# Conn_B.net
KiCad netlist of a schematic drawn in Altium Designer
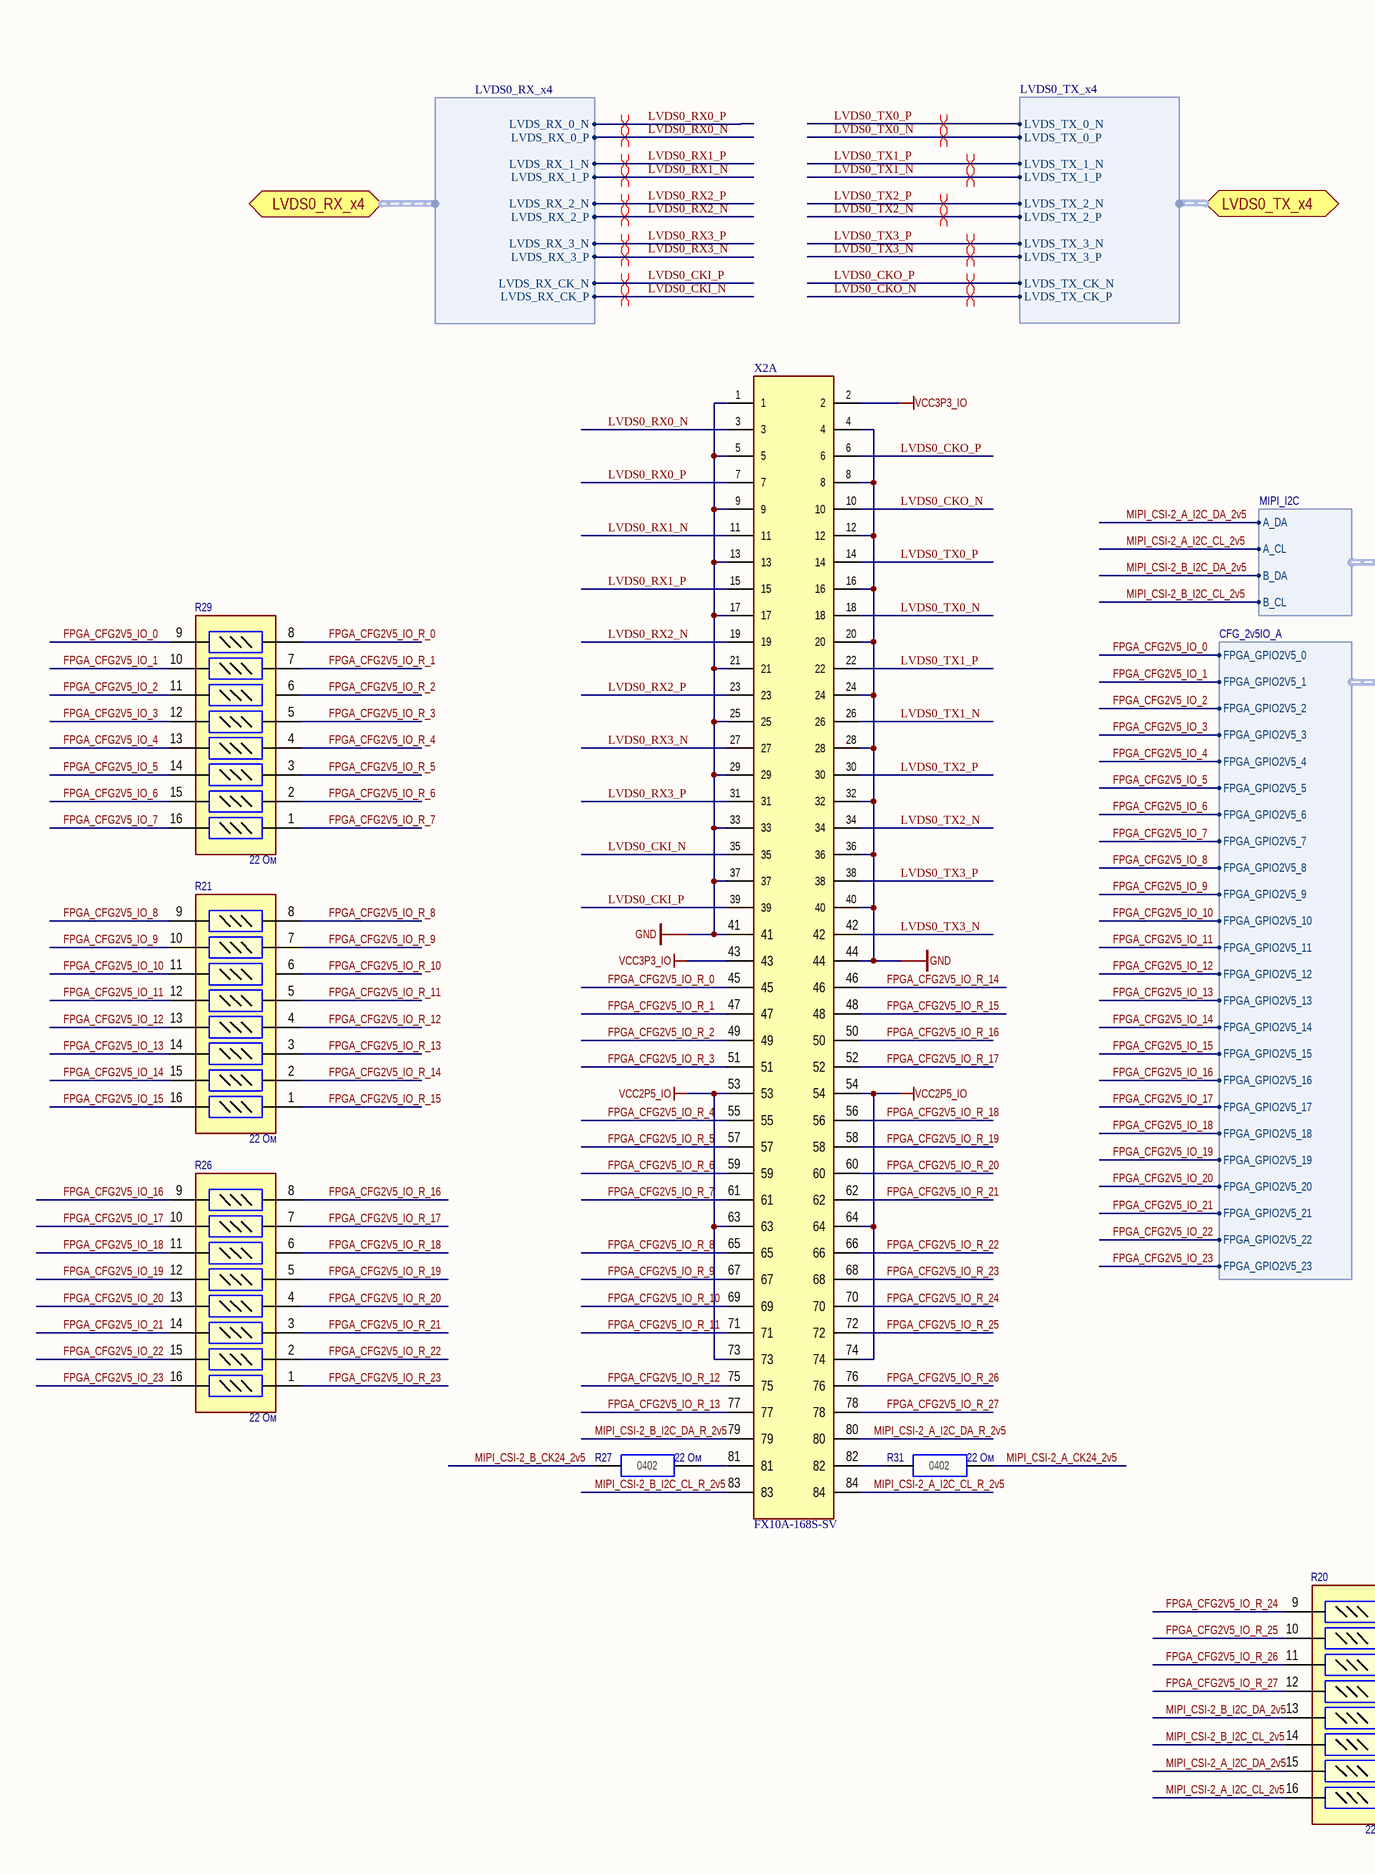
[diagram p0: Conn_B.SchDoc, left]
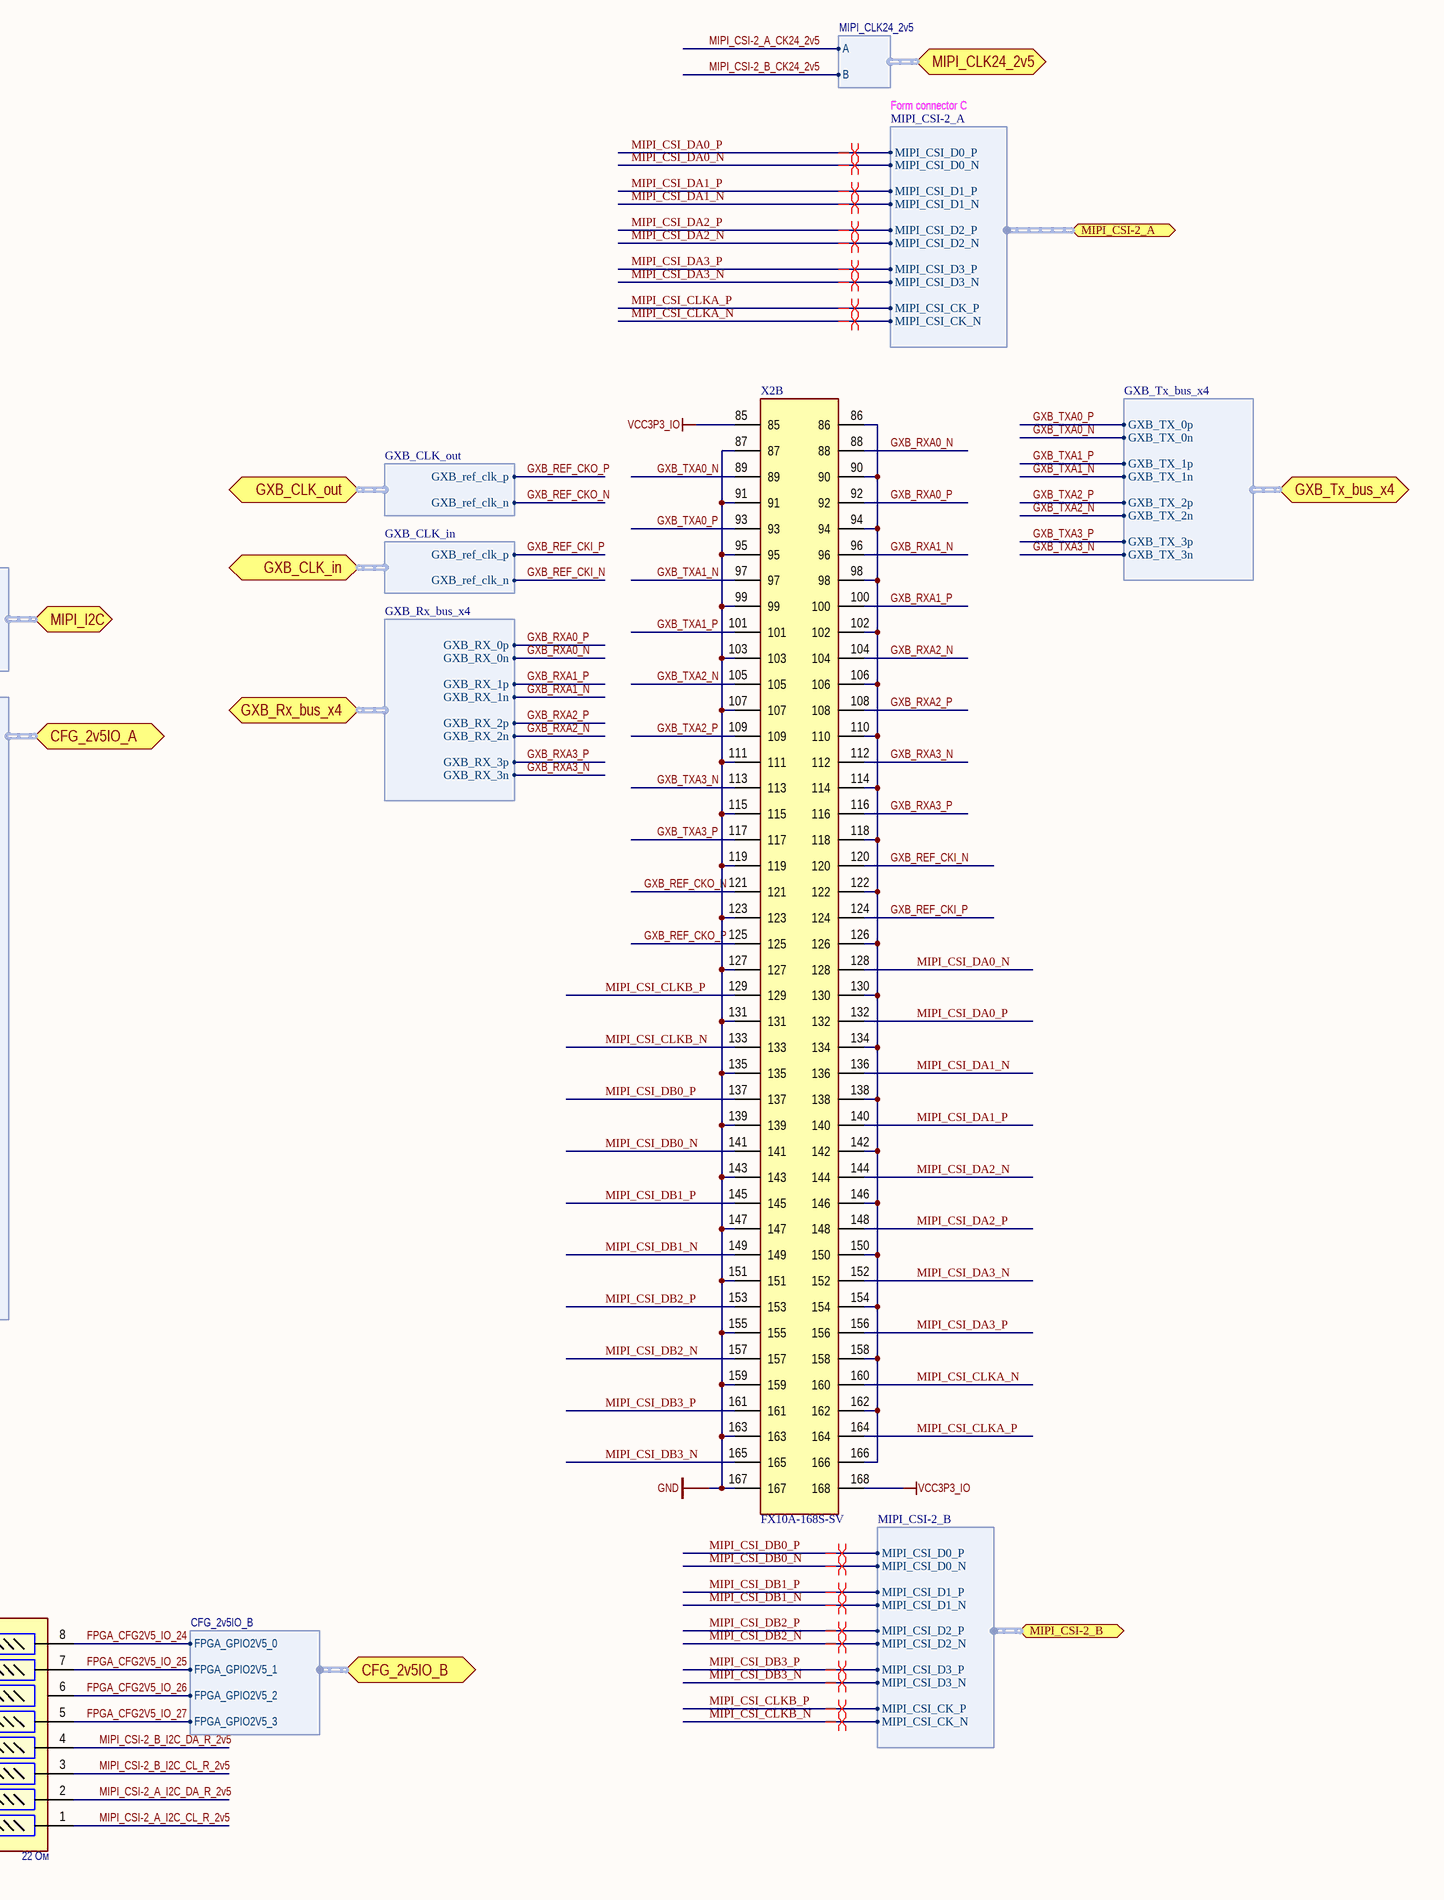
[diagram p1: Conn_B.SchDoc, right]

(export (version "E")
  (design (tool "Eeschema 10.0.6"))
  (components
    (comp (ref "R20")
      (value "22 Ом")
      (footprint "CAT16-J8")
      (description "Набор чип резисторов")
      (fields (field (name "Comment") "YC248-JR-07-22 Ом"))
      (libsource (lib "SD_IC") (part "YC248-JR-07-#"))
    )
    (comp (ref "R21")
      (value "22 Ом")
      (footprint "CAT16-J8")
      (description "Набор чип резисторов")
      (fields (field (name "Comment") "YC248-JR-07-22 Ом"))
      (libsource (lib "SD_IC") (part "YC248-JR-07-#"))
    )
    (comp (ref "R26")
      (value "22 Ом")
      (footprint "CAT16-J8")
      (description "Набор чип резисторов")
      (fields (field (name "Comment") "YC248-JR-07-22 Ом"))
      (libsource (lib "SD_IC") (part "YC248-JR-07-#"))
    )
    (comp (ref "R27")
      (value "22 Ом")
      (footprint "CR0402(1005)")
      (description "Чип резистор")
      (fields (field (name "TOLERANCE") "5%") (field (name "Comment") "CR0402-22 Ом-±5%"))
      (libsource (lib "Чип резисторы") (part "CR0402-#-±5%"))
    )
    (comp (ref "R29")
      (value "22 Ом")
      (footprint "CAT16-J8")
      (description "Набор чип резисторов")
      (fields (field (name "Comment") "YC248-JR-07-22 Ом"))
      (libsource (lib "SD_IC") (part "YC248-JR-07-#"))
    )
    (comp (ref "R31")
      (value "22 Ом")
      (footprint "CR0402(1005)")
      (description "Чип резистор")
      (fields (field (name "TOLERANCE") "5%") (field (name "Comment") "CR0402-22 Ом-±5%"))
      (libsource (lib "Чип резисторы") (part "CR0402-#-±5%"))
    )
    (comp (ref "X2")
      (value "FX10A-168S-SV")
      (footprint "FX10A-168S-SV")
      (libsource (lib "SD_IC") (part "FX10A-168S-SV"))
    )
  )
  (nets
    (net (code "13") (name "/FPGA_CFG2V5_IO_0") (class "Default")
      (node (ref "R29") (pin "9") (pintype "passive"))
    )
    (net (code "14") (name "/FPGA_CFG2V5_IO_1") (class "Default")
      (node (ref "R29") (pin "10") (pintype "passive"))
    )
    (net (code "15") (name "/FPGA_CFG2V5_IO_2") (class "Default")
      (node (ref "R29") (pin "11") (pintype "passive"))
    )
    (net (code "16") (name "/FPGA_CFG2V5_IO_3") (class "Default")
      (node (ref "R29") (pin "12") (pintype "passive"))
    )
    (net (code "17") (name "/FPGA_CFG2V5_IO_4") (class "Default")
      (node (ref "R29") (pin "13") (pintype "passive"))
    )
    (net (code "18") (name "/FPGA_CFG2V5_IO_5") (class "Default")
      (node (ref "R29") (pin "14") (pintype "passive"))
    )
    (net (code "19") (name "/FPGA_CFG2V5_IO_6") (class "Default")
      (node (ref "R29") (pin "15") (pintype "passive"))
    )
    (net (code "20") (name "/FPGA_CFG2V5_IO_7") (class "Default")
      (node (ref "R29") (pin "16") (pintype "passive"))
    )
    (net (code "21") (name "/FPGA_CFG2V5_IO_8") (class "Default")
      (node (ref "R21") (pin "9") (pintype "passive"))
    )
    (net (code "22") (name "/FPGA_CFG2V5_IO_9") (class "Default")
      (node (ref "R21") (pin "10") (pintype "passive"))
    )
    (net (code "23") (name "/FPGA_CFG2V5_IO_10") (class "Default")
      (node (ref "R21") (pin "11") (pintype "passive"))
    )
    (net (code "24") (name "/FPGA_CFG2V5_IO_11") (class "Default")
      (node (ref "R21") (pin "12") (pintype "passive"))
    )
    (net (code "25") (name "/FPGA_CFG2V5_IO_12") (class "Default")
      (node (ref "R21") (pin "13") (pintype "passive"))
    )
    (net (code "26") (name "/FPGA_CFG2V5_IO_13") (class "Default")
      (node (ref "R21") (pin "14") (pintype "passive"))
    )
    (net (code "27") (name "/FPGA_CFG2V5_IO_14") (class "Default")
      (node (ref "R21") (pin "15") (pintype "passive"))
    )
    (net (code "28") (name "/FPGA_CFG2V5_IO_15") (class "Default")
      (node (ref "R21") (pin "16") (pintype "passive"))
    )
    (net (code "29") (name "/FPGA_CFG2V5_IO_16") (class "Default")
      (node (ref "R26") (pin "9") (pintype "passive"))
    )
    (net (code "30") (name "/FPGA_CFG2V5_IO_17") (class "Default")
      (node (ref "R26") (pin "10") (pintype "passive"))
    )
    (net (code "31") (name "/FPGA_CFG2V5_IO_18") (class "Default")
      (node (ref "R26") (pin "11") (pintype "passive"))
    )
    (net (code "32") (name "/FPGA_CFG2V5_IO_19") (class "Default")
      (node (ref "R26") (pin "12") (pintype "passive"))
    )
    (net (code "33") (name "/FPGA_CFG2V5_IO_20") (class "Default")
      (node (ref "R26") (pin "13") (pintype "passive"))
    )
    (net (code "34") (name "/FPGA_CFG2V5_IO_21") (class "Default")
      (node (ref "R26") (pin "14") (pintype "passive"))
    )
    (net (code "35") (name "/FPGA_CFG2V5_IO_22") (class "Default")
      (node (ref "R26") (pin "15") (pintype "passive"))
    )
    (net (code "36") (name "/FPGA_CFG2V5_IO_23") (class "Default")
      (node (ref "R26") (pin "16") (pintype "passive"))
    )
    (net (code "37") (name "/FPGA_CFG2V5_IO_24") (class "Default")
      (node (ref "R20") (pin "8") (pintype "passive"))
    )
    (net (code "38") (name "/FPGA_CFG2V5_IO_25") (class "Default")
      (node (ref "R20") (pin "7") (pintype "passive"))
    )
    (net (code "39") (name "/FPGA_CFG2V5_IO_26") (class "Default")
      (node (ref "R20") (pin "6") (pintype "passive"))
    )
    (net (code "40") (name "/FPGA_CFG2V5_IO_27") (class "Default")
      (node (ref "R20") (pin "5") (pintype "passive"))
    )
    (net (code "41") (name "/FPGA_CFG2V5_IO_R_0") (class "Default")
      (node (ref "R29") (pin "8") (pintype "passive"))
      (node (ref "X2") (pin "45") (pinfunction "45_45") (pintype "passive"))
    )
    (net (code "42") (name "/FPGA_CFG2V5_IO_R_1") (class "Default")
      (node (ref "R29") (pin "7") (pintype "passive"))
      (node (ref "X2") (pin "47") (pinfunction "47_47") (pintype "passive"))
    )
    (net (code "43") (name "/FPGA_CFG2V5_IO_R_2") (class "Default")
      (node (ref "R29") (pin "6") (pintype "passive"))
      (node (ref "X2") (pin "49") (pinfunction "49_49") (pintype "passive"))
    )
    (net (code "44") (name "/FPGA_CFG2V5_IO_R_3") (class "Default")
      (node (ref "R29") (pin "5") (pintype "passive"))
      (node (ref "X2") (pin "51") (pinfunction "51_51") (pintype "passive"))
    )
    (net (code "45") (name "/FPGA_CFG2V5_IO_R_4") (class "Default")
      (node (ref "R29") (pin "4") (pintype "passive"))
      (node (ref "X2") (pin "55") (pinfunction "55_55") (pintype "passive"))
    )
    (net (code "46") (name "/FPGA_CFG2V5_IO_R_5") (class "Default")
      (node (ref "R29") (pin "3") (pintype "passive"))
      (node (ref "X2") (pin "57") (pinfunction "57_57") (pintype "passive"))
    )
    (net (code "47") (name "/FPGA_CFG2V5_IO_R_6") (class "Default")
      (node (ref "R29") (pin "2") (pintype "passive"))
      (node (ref "X2") (pin "59") (pinfunction "59_59") (pintype "passive"))
    )
    (net (code "48") (name "/FPGA_CFG2V5_IO_R_7") (class "Default")
      (node (ref "R29") (pin "1") (pintype "passive"))
      (node (ref "X2") (pin "61") (pinfunction "61_61") (pintype "passive"))
    )
    (net (code "49") (name "/FPGA_CFG2V5_IO_R_8") (class "Default")
      (node (ref "R21") (pin "8") (pintype "passive"))
      (node (ref "X2") (pin "65") (pinfunction "65_65") (pintype "passive"))
    )
    (net (code "50") (name "/FPGA_CFG2V5_IO_R_9") (class "Default")
      (node (ref "R21") (pin "7") (pintype "passive"))
      (node (ref "X2") (pin "67") (pinfunction "67_67") (pintype "passive"))
    )
    (net (code "51") (name "/FPGA_CFG2V5_IO_R_10") (class "Default")
      (node (ref "R21") (pin "6") (pintype "passive"))
      (node (ref "X2") (pin "69") (pinfunction "69_69") (pintype "passive"))
    )
    (net (code "52") (name "/FPGA_CFG2V5_IO_R_11") (class "Default")
      (node (ref "R21") (pin "5") (pintype "passive"))
      (node (ref "X2") (pin "71") (pinfunction "71_71") (pintype "passive"))
    )
    (net (code "53") (name "/FPGA_CFG2V5_IO_R_12") (class "Default")
      (node (ref "R21") (pin "4") (pintype "passive"))
      (node (ref "X2") (pin "75") (pinfunction "75_75") (pintype "passive"))
    )
    (net (code "54") (name "/FPGA_CFG2V5_IO_R_13") (class "Default")
      (node (ref "R21") (pin "3") (pintype "passive"))
      (node (ref "X2") (pin "77") (pinfunction "77_77") (pintype "passive"))
    )
    (net (code "55") (name "/FPGA_CFG2V5_IO_R_14") (class "Default")
      (node (ref "R21") (pin "2") (pintype "passive"))
      (node (ref "X2") (pin "46") (pinfunction "46_46") (pintype "passive"))
    )
    (net (code "56") (name "/FPGA_CFG2V5_IO_R_15") (class "Default")
      (node (ref "R21") (pin "1") (pintype "passive"))
      (node (ref "X2") (pin "48") (pinfunction "48_48") (pintype "passive"))
    )
    (net (code "57") (name "/FPGA_CFG2V5_IO_R_16") (class "Default")
      (node (ref "R26") (pin "8") (pintype "passive"))
      (node (ref "X2") (pin "50") (pinfunction "50_50") (pintype "passive"))
    )
    (net (code "58") (name "/FPGA_CFG2V5_IO_R_17") (class "Default")
      (node (ref "R26") (pin "7") (pintype "passive"))
      (node (ref "X2") (pin "52") (pinfunction "52_52") (pintype "passive"))
    )
    (net (code "59") (name "/FPGA_CFG2V5_IO_R_18") (class "Default")
      (node (ref "R26") (pin "6") (pintype "passive"))
      (node (ref "X2") (pin "56") (pinfunction "56_56") (pintype "passive"))
    )
    (net (code "60") (name "/FPGA_CFG2V5_IO_R_19") (class "Default")
      (node (ref "R26") (pin "5") (pintype "passive"))
      (node (ref "X2") (pin "58") (pinfunction "58_58") (pintype "passive"))
    )
    (net (code "61") (name "/FPGA_CFG2V5_IO_R_20") (class "Default")
      (node (ref "R26") (pin "4") (pintype "passive"))
      (node (ref "X2") (pin "60") (pinfunction "60_60") (pintype "passive"))
    )
    (net (code "62") (name "/FPGA_CFG2V5_IO_R_21") (class "Default")
      (node (ref "R26") (pin "3") (pintype "passive"))
      (node (ref "X2") (pin "62") (pinfunction "62_62") (pintype "passive"))
    )
    (net (code "63") (name "/FPGA_CFG2V5_IO_R_22") (class "Default")
      (node (ref "R26") (pin "2") (pintype "passive"))
      (node (ref "X2") (pin "66") (pinfunction "66_66") (pintype "passive"))
    )
    (net (code "64") (name "/FPGA_CFG2V5_IO_R_23") (class "Default")
      (node (ref "R26") (pin "1") (pintype "passive"))
      (node (ref "X2") (pin "68") (pinfunction "68_68") (pintype "passive"))
    )
    (net (code "65") (name "/FPGA_CFG2V5_IO_R_24") (class "Default")
      (node (ref "R20") (pin "9") (pintype "passive"))
      (node (ref "X2") (pin "70") (pinfunction "70_70") (pintype "passive"))
    )
    (net (code "66") (name "/FPGA_CFG2V5_IO_R_25") (class "Default")
      (node (ref "R20") (pin "10") (pintype "passive"))
      (node (ref "X2") (pin "72") (pinfunction "72_72") (pintype "passive"))
    )
    (net (code "67") (name "/FPGA_CFG2V5_IO_R_26") (class "Default")
      (node (ref "R20") (pin "11") (pintype "passive"))
      (node (ref "X2") (pin "76") (pinfunction "76_76") (pintype "passive"))
    )
    (net (code "68") (name "/FPGA_CFG2V5_IO_R_27") (class "Default")
      (node (ref "R20") (pin "12") (pintype "passive"))
      (node (ref "X2") (pin "78") (pinfunction "78_78") (pintype "passive"))
    )
    (net (code "69") (name "/GXB_REF_CKI_N") (class "Default")
      (node (ref "X2") (pin "120") (pinfunction "120_120") (pintype "passive"))
    )
    (net (code "70") (name "/GXB_REF_CKI_P") (class "Default")
      (node (ref "X2") (pin "124") (pinfunction "124_124") (pintype "passive"))
    )
    (net (code "71") (name "/GXB_REF_CKO_N") (class "Default")
      (node (ref "X2") (pin "121") (pinfunction "121_121") (pintype "passive"))
    )
    (net (code "72") (name "/GXB_REF_CKO_P") (class "Default")
      (node (ref "X2") (pin "125") (pinfunction "125_125") (pintype "passive"))
    )
    (net (code "73") (name "/GXB_RXA0_N") (class "Default")
      (node (ref "X2") (pin "88") (pinfunction "88_88") (pintype "passive"))
    )
    (net (code "74") (name "/GXB_RXA0_P") (class "Default")
      (node (ref "X2") (pin "92") (pinfunction "92_92") (pintype "passive"))
    )
    (net (code "75") (name "/GXB_RXA1_N") (class "Default")
      (node (ref "X2") (pin "96") (pinfunction "96_96") (pintype "passive"))
    )
    (net (code "76") (name "/GXB_RXA1_P") (class "Default")
      (node (ref "X2") (pin "100") (pinfunction "100_100") (pintype "passive"))
    )
    (net (code "77") (name "/GXB_RXA2_N") (class "Default")
      (node (ref "X2") (pin "104") (pinfunction "104_104") (pintype "passive"))
    )
    (net (code "78") (name "/GXB_RXA2_P") (class "Default")
      (node (ref "X2") (pin "108") (pinfunction "108_108") (pintype "passive"))
    )
    (net (code "79") (name "/GXB_RXA3_N") (class "Default")
      (node (ref "X2") (pin "112") (pinfunction "112_112") (pintype "passive"))
    )
    (net (code "80") (name "/GXB_RXA3_P") (class "Default")
      (node (ref "X2") (pin "116") (pinfunction "116_116") (pintype "passive"))
    )
    (net (code "81") (name "/GXB_TXA0_N") (class "Default")
      (node (ref "X2") (pin "89") (pinfunction "89_89") (pintype "passive"))
    )
    (net (code "82") (name "/GXB_TXA0_P") (class "Default")
      (node (ref "X2") (pin "93") (pinfunction "93_93") (pintype "passive"))
    )
    (net (code "83") (name "/GXB_TXA1_N") (class "Default")
      (node (ref "X2") (pin "97") (pinfunction "97_97") (pintype "passive"))
    )
    (net (code "84") (name "/GXB_TXA1_P") (class "Default")
      (node (ref "X2") (pin "101") (pinfunction "101_101") (pintype "passive"))
    )
    (net (code "85") (name "/GXB_TXA2_N") (class "Default")
      (node (ref "X2") (pin "105") (pinfunction "105_105") (pintype "passive"))
    )
    (net (code "86") (name "/GXB_TXA2_P") (class "Default")
      (node (ref "X2") (pin "109") (pinfunction "109_109") (pintype "passive"))
    )
    (net (code "87") (name "/GXB_TXA3_N") (class "Default")
      (node (ref "X2") (pin "113") (pinfunction "113_113") (pintype "passive"))
    )
    (net (code "88") (name "/GXB_TXA3_P") (class "Default")
      (node (ref "X2") (pin "117") (pinfunction "117_117") (pintype "passive"))
    )
    (net (code "89") (name "/LVDS0_CKI_N") (class "Default")
      (node (ref "X2") (pin "35") (pinfunction "35_35") (pintype "passive"))
    )
    (net (code "90") (name "/LVDS0_CKI_P") (class "Default")
      (node (ref "X2") (pin "39") (pinfunction "39_39") (pintype "passive"))
    )
    (net (code "91") (name "/LVDS0_CKO_N") (class "Default")
      (node (ref "X2") (pin "10") (pinfunction "10_10") (pintype "passive"))
    )
    (net (code "92") (name "/LVDS0_CKO_P") (class "Default")
      (node (ref "X2") (pin "6") (pinfunction "6_6") (pintype "passive"))
    )
    (net (code "93") (name "/LVDS0_RX0_N") (class "Default")
      (node (ref "X2") (pin "3") (pinfunction "3_3") (pintype "passive"))
    )
    (net (code "94") (name "/LVDS0_RX0_P") (class "Default")
      (node (ref "X2") (pin "7") (pinfunction "7_7") (pintype "passive"))
    )
    (net (code "95") (name "/LVDS0_RX1_N") (class "Default")
      (node (ref "X2") (pin "11") (pinfunction "11_11") (pintype "passive"))
    )
    (net (code "96") (name "/LVDS0_RX1_P") (class "Default")
      (node (ref "X2") (pin "15") (pinfunction "15_15") (pintype "passive"))
    )
    (net (code "97") (name "/LVDS0_RX2_N") (class "Default")
      (node (ref "X2") (pin "19") (pinfunction "19_19") (pintype "passive"))
    )
    (net (code "98") (name "/LVDS0_RX2_P") (class "Default")
      (node (ref "X2") (pin "23") (pinfunction "23_23") (pintype "passive"))
    )
    (net (code "99") (name "/LVDS0_RX3_N") (class "Default")
      (node (ref "X2") (pin "27") (pinfunction "27_27") (pintype "passive"))
    )
    (net (code "100") (name "/LVDS0_RX3_P") (class "Default")
      (node (ref "X2") (pin "31") (pinfunction "31_31") (pintype "passive"))
    )
    (net (code "101") (name "/LVDS0_TX0_N") (class "Default")
      (node (ref "X2") (pin "18") (pinfunction "18_18") (pintype "passive"))
    )
    (net (code "102") (name "/LVDS0_TX0_P") (class "Default")
      (node (ref "X2") (pin "14") (pinfunction "14_14") (pintype "passive"))
    )
    (net (code "103") (name "/LVDS0_TX1_N") (class "Default")
      (node (ref "X2") (pin "26") (pinfunction "26_26") (pintype "passive"))
    )
    (net (code "104") (name "/LVDS0_TX1_P") (class "Default")
      (node (ref "X2") (pin "22") (pinfunction "22_22") (pintype "passive"))
    )
    (net (code "105") (name "/LVDS0_TX2_N") (class "Default")
      (node (ref "X2") (pin "34") (pinfunction "34_34") (pintype "passive"))
    )
    (net (code "106") (name "/LVDS0_TX2_P") (class "Default")
      (node (ref "X2") (pin "30") (pinfunction "30_30") (pintype "passive"))
    )
    (net (code "107") (name "/LVDS0_TX3_N") (class "Default")
      (node (ref "X2") (pin "42") (pinfunction "42_42") (pintype "passive"))
    )
    (net (code "108") (name "/LVDS0_TX3_P") (class "Default")
      (node (ref "X2") (pin "38") (pinfunction "38_38") (pintype "passive"))
    )
    (net (code "109") (name "/MIPI_CSI-2_A_CK24_2v5") (class "Default")
      (node (ref "R31") (pin "2") (pinfunction "-_2") (pintype "passive"))
    )
    (net (code "110") (name "/MIPI_CSI-2_A_I2C_CL_2v5") (class "Default")
      (node (ref "R20") (pin "16") (pintype "passive"))
    )
    (net (code "111") (name "/MIPI_CSI-2_A_I2C_CL_R_2v5") (class "Default")
      (node (ref "R20") (pin "1") (pintype "passive"))
      (node (ref "X2") (pin "84") (pinfunction "84_84") (pintype "passive"))
    )
    (net (code "112") (name "/MIPI_CSI-2_A_I2C_DA_2v5") (class "Default")
      (node (ref "R20") (pin "15") (pintype "passive"))
    )
    (net (code "113") (name "/MIPI_CSI-2_A_I2C_DA_R_2v5") (class "Default")
      (node (ref "R20") (pin "2") (pintype "passive"))
      (node (ref "X2") (pin "80") (pinfunction "80_80") (pintype "passive"))
    )
    (net (code "114") (name "/MIPI_CSI-2_B_CK24_2v5") (class "Default")
      (node (ref "R27") (pin "1") (pinfunction "+_1") (pintype "passive"))
    )
    (net (code "115") (name "/MIPI_CSI-2_B_I2C_CL_2v5") (class "Default")
      (node (ref "R20") (pin "14") (pintype "passive"))
    )
    (net (code "116") (name "/MIPI_CSI-2_B_I2C_CL_R_2v5") (class "Default")
      (node (ref "R20") (pin "3") (pintype "passive"))
      (node (ref "X2") (pin "83") (pinfunction "83_83") (pintype "passive"))
    )
    (net (code "117") (name "/MIPI_CSI-2_B_I2C_DA_2v5") (class "Default")
      (node (ref "R20") (pin "13") (pintype "passive"))
    )
    (net (code "118") (name "/MIPI_CSI-2_B_I2C_DA_R_2v5") (class "Default")
      (node (ref "R20") (pin "4") (pintype "passive"))
      (node (ref "X2") (pin "79") (pinfunction "79_79") (pintype "passive"))
    )
    (net (code "119") (name "/MIPI_CSI_CLKA_N") (class "Default")
      (node (ref "X2") (pin "160") (pinfunction "160_160") (pintype "passive"))
    )
    (net (code "120") (name "/MIPI_CSI_CLKA_P") (class "Default")
      (node (ref "X2") (pin "164") (pinfunction "164_164") (pintype "passive"))
    )
    (net (code "121") (name "/MIPI_CSI_CLKB_N") (class "Default")
      (node (ref "X2") (pin "133") (pinfunction "133_133") (pintype "passive"))
    )
    (net (code "122") (name "/MIPI_CSI_CLKB_P") (class "Default")
      (node (ref "X2") (pin "129") (pinfunction "129_129") (pintype "passive"))
    )
    (net (code "123") (name "/MIPI_CSI_DA0_N") (class "Default")
      (node (ref "X2") (pin "128") (pinfunction "128_128") (pintype "passive"))
    )
    (net (code "124") (name "/MIPI_CSI_DA0_P") (class "Default")
      (node (ref "X2") (pin "132") (pinfunction "132_132") (pintype "passive"))
    )
    (net (code "125") (name "/MIPI_CSI_DA1_N") (class "Default")
      (node (ref "X2") (pin "136") (pinfunction "136_136") (pintype "passive"))
    )
    (net (code "126") (name "/MIPI_CSI_DA1_P") (class "Default")
      (node (ref "X2") (pin "140") (pinfunction "140_140") (pintype "passive"))
    )
    (net (code "127") (name "/MIPI_CSI_DA2_N") (class "Default")
      (node (ref "X2") (pin "144") (pinfunction "144_144") (pintype "passive"))
    )
    (net (code "128") (name "/MIPI_CSI_DA2_P") (class "Default")
      (node (ref "X2") (pin "148") (pinfunction "148_148") (pintype "passive"))
    )
    (net (code "129") (name "/MIPI_CSI_DA3_N") (class "Default")
      (node (ref "X2") (pin "152") (pinfunction "152_152") (pintype "passive"))
    )
    (net (code "130") (name "/MIPI_CSI_DA3_P") (class "Default")
      (node (ref "X2") (pin "156") (pinfunction "156_156") (pintype "passive"))
    )
    (net (code "131") (name "/MIPI_CSI_DB0_N") (class "Default")
      (node (ref "X2") (pin "141") (pinfunction "141_141") (pintype "passive"))
    )
    (net (code "132") (name "/MIPI_CSI_DB0_P") (class "Default")
      (node (ref "X2") (pin "137") (pinfunction "137_137") (pintype "passive"))
    )
    (net (code "133") (name "/MIPI_CSI_DB1_N") (class "Default")
      (node (ref "X2") (pin "149") (pinfunction "149_149") (pintype "passive"))
    )
    (net (code "134") (name "/MIPI_CSI_DB1_P") (class "Default")
      (node (ref "X2") (pin "145") (pinfunction "145_145") (pintype "passive"))
    )
    (net (code "135") (name "/MIPI_CSI_DB2_N") (class "Default")
      (node (ref "X2") (pin "157") (pinfunction "157_157") (pintype "passive"))
    )
    (net (code "136") (name "/MIPI_CSI_DB2_P") (class "Default")
      (node (ref "X2") (pin "153") (pinfunction "153_153") (pintype "passive"))
    )
    (net (code "137") (name "/MIPI_CSI_DB3_N") (class "Default")
      (node (ref "X2") (pin "165") (pinfunction "165_165") (pintype "passive"))
    )
    (net (code "138") (name "/MIPI_CSI_DB3_P") (class "Default")
      (node (ref "X2") (pin "161") (pinfunction "161_161") (pintype "passive"))
    )
    (net (code "151") (name "GND") (class "Default")
      (node (ref "X2") (pin "1") (pinfunction "1_1") (pintype "passive"))
      (node (ref "X2") (pin "103") (pinfunction "103_103") (pintype "passive"))
      (node (ref "X2") (pin "107") (pinfunction "107_107") (pintype "passive"))
      (node (ref "X2") (pin "111") (pinfunction "111_111") (pintype "passive"))
      (node (ref "X2") (pin "115") (pinfunction "115_115") (pintype "passive"))
      (node (ref "X2") (pin "119") (pinfunction "119_119") (pintype "passive"))
      (node (ref "X2") (pin "12") (pinfunction "12_12") (pintype "passive"))
      (node (ref "X2") (pin "123") (pinfunction "123_123") (pintype "passive"))
      (node (ref "X2") (pin "127") (pinfunction "127_127") (pintype "passive"))
      (node (ref "X2") (pin "13") (pinfunction "13_13") (pintype "passive"))
      (node (ref "X2") (pin "131") (pinfunction "131_131") (pintype "passive"))
      (node (ref "X2") (pin "135") (pinfunction "135_135") (pintype "passive"))
      (node (ref "X2") (pin "139") (pinfunction "139_139") (pintype "passive"))
      (node (ref "X2") (pin "143") (pinfunction "143_143") (pintype "passive"))
      (node (ref "X2") (pin "147") (pinfunction "147_147") (pintype "passive"))
      (node (ref "X2") (pin "151") (pinfunction "151_151") (pintype "passive"))
      (node (ref "X2") (pin "155") (pinfunction "155_155") (pintype "passive"))
      (node (ref "X2") (pin "159") (pinfunction "159_159") (pintype "passive"))
      (node (ref "X2") (pin "16") (pinfunction "16_16") (pintype "passive"))
      (node (ref "X2") (pin "163") (pinfunction "163_163") (pintype "passive"))
      (node (ref "X2") (pin "167") (pinfunction "167_167") (pintype "passive"))
      (node (ref "X2") (pin "17") (pinfunction "17_17") (pintype "passive"))
      (node (ref "X2") (pin "20") (pinfunction "20_20") (pintype "passive"))
      (node (ref "X2") (pin "21") (pinfunction "21_21") (pintype "passive"))
      (node (ref "X2") (pin "24") (pinfunction "24_24") (pintype "passive"))
      (node (ref "X2") (pin "25") (pinfunction "25_25") (pintype "passive"))
      (node (ref "X2") (pin "28") (pinfunction "28_28") (pintype "passive"))
      (node (ref "X2") (pin "29") (pinfunction "29_29") (pintype "passive"))
      (node (ref "X2") (pin "32") (pinfunction "32_32") (pintype "passive"))
      (node (ref "X2") (pin "33") (pinfunction "33_33") (pintype "passive"))
      (node (ref "X2") (pin "36") (pinfunction "36_36") (pintype "passive"))
      (node (ref "X2") (pin "37") (pinfunction "37_37") (pintype "passive"))
      (node (ref "X2") (pin "4") (pinfunction "4_4") (pintype "passive"))
      (node (ref "X2") (pin "40") (pinfunction "40_40") (pintype "passive"))
      (node (ref "X2") (pin "41") (pinfunction "41_41") (pintype "passive"))
      (node (ref "X2") (pin "44") (pinfunction "44_44") (pintype "passive"))
      (node (ref "X2") (pin "5") (pinfunction "5_5") (pintype "passive"))
      (node (ref "X2") (pin "8") (pinfunction "8_8") (pintype "passive"))
      (node (ref "X2") (pin "87") (pinfunction "87_87") (pintype "passive"))
      (node (ref "X2") (pin "9") (pinfunction "9_9") (pintype "passive"))
      (node (ref "X2") (pin "91") (pinfunction "91_91") (pintype "passive"))
      (node (ref "X2") (pin "95") (pinfunction "95_95") (pintype "passive"))
      (node (ref "X2") (pin "99") (pinfunction "99_99") (pintype "passive"))
    )
    (net (code "152") (name "Net-(R27--)") (class "Default")
      (node (ref "R27") (pin "2") (pinfunction "-_2") (pintype "passive"))
      (node (ref "X2") (pin "81") (pinfunction "81_81") (pintype "passive"))
    )
    (net (code "153") (name "Net-(R31-+)") (class "Default")
      (node (ref "R31") (pin "1") (pinfunction "+_1") (pintype "passive"))
      (node (ref "X2") (pin "82") (pinfunction "82_82") (pintype "passive"))
    )
    (net (code "154") (name "Net-(X2-Pad102)") (class "Default")
      (node (ref "X2") (pin "102") (pinfunction "102_102") (pintype "passive"))
      (node (ref "X2") (pin "106") (pinfunction "106_106") (pintype "passive"))
      (node (ref "X2") (pin "110") (pinfunction "110_110") (pintype "passive"))
      (node (ref "X2") (pin "114") (pinfunction "114_114") (pintype "passive"))
      (node (ref "X2") (pin "118") (pinfunction "118_118") (pintype "passive"))
      (node (ref "X2") (pin "122") (pinfunction "122_122") (pintype "passive"))
      (node (ref "X2") (pin "126") (pinfunction "126_126") (pintype "passive"))
      (node (ref "X2") (pin "130") (pinfunction "130_130") (pintype "passive"))
      (node (ref "X2") (pin "134") (pinfunction "134_134") (pintype "passive"))
      (node (ref "X2") (pin "138") (pinfunction "138_138") (pintype "passive"))
      (node (ref "X2") (pin "142") (pinfunction "142_142") (pintype "passive"))
      (node (ref "X2") (pin "146") (pinfunction "146_146") (pintype "passive"))
      (node (ref "X2") (pin "150") (pinfunction "150_150") (pintype "passive"))
      (node (ref "X2") (pin "154") (pinfunction "154_154") (pintype "passive"))
      (node (ref "X2") (pin "158") (pinfunction "158_158") (pintype "passive"))
      (node (ref "X2") (pin "162") (pinfunction "162_162") (pintype "passive"))
      (node (ref "X2") (pin "166") (pinfunction "166_166") (pintype "passive"))
      (node (ref "X2") (pin "86") (pinfunction "86_86") (pintype "passive"))
      (node (ref "X2") (pin "90") (pinfunction "90_90") (pintype "passive"))
      (node (ref "X2") (pin "94") (pinfunction "94_94") (pintype "passive"))
      (node (ref "X2") (pin "98") (pinfunction "98_98") (pintype "passive"))
    )
    (net (code "155") (name "VCC2P5_IO") (class "Default")
      (node (ref "X2") (pin "53") (pinfunction "53_53") (pintype "passive"))
      (node (ref "X2") (pin "54") (pinfunction "54_54") (pintype "passive"))
      (node (ref "X2") (pin "63") (pinfunction "63_63") (pintype "passive"))
      (node (ref "X2") (pin "64") (pinfunction "64_64") (pintype "passive"))
      (node (ref "X2") (pin "73") (pinfunction "73_73") (pintype "passive"))
      (node (ref "X2") (pin "74") (pinfunction "74_74") (pintype "passive"))
    )
    (net (code "156") (name "VCC3P3_IO") (class "Default")
      (node (ref "X2") (pin "168") (pinfunction "168_168") (pintype "passive"))
      (node (ref "X2") (pin "2") (pinfunction "2_2") (pintype "passive"))
      (node (ref "X2") (pin "43") (pinfunction "43_43") (pintype "passive"))
      (node (ref "X2") (pin "85") (pinfunction "85_85") (pintype "passive"))
    )
  )
)
